# Carriage_Board_V3.net
KiCad netlist of a schematic drawn in EAGLE
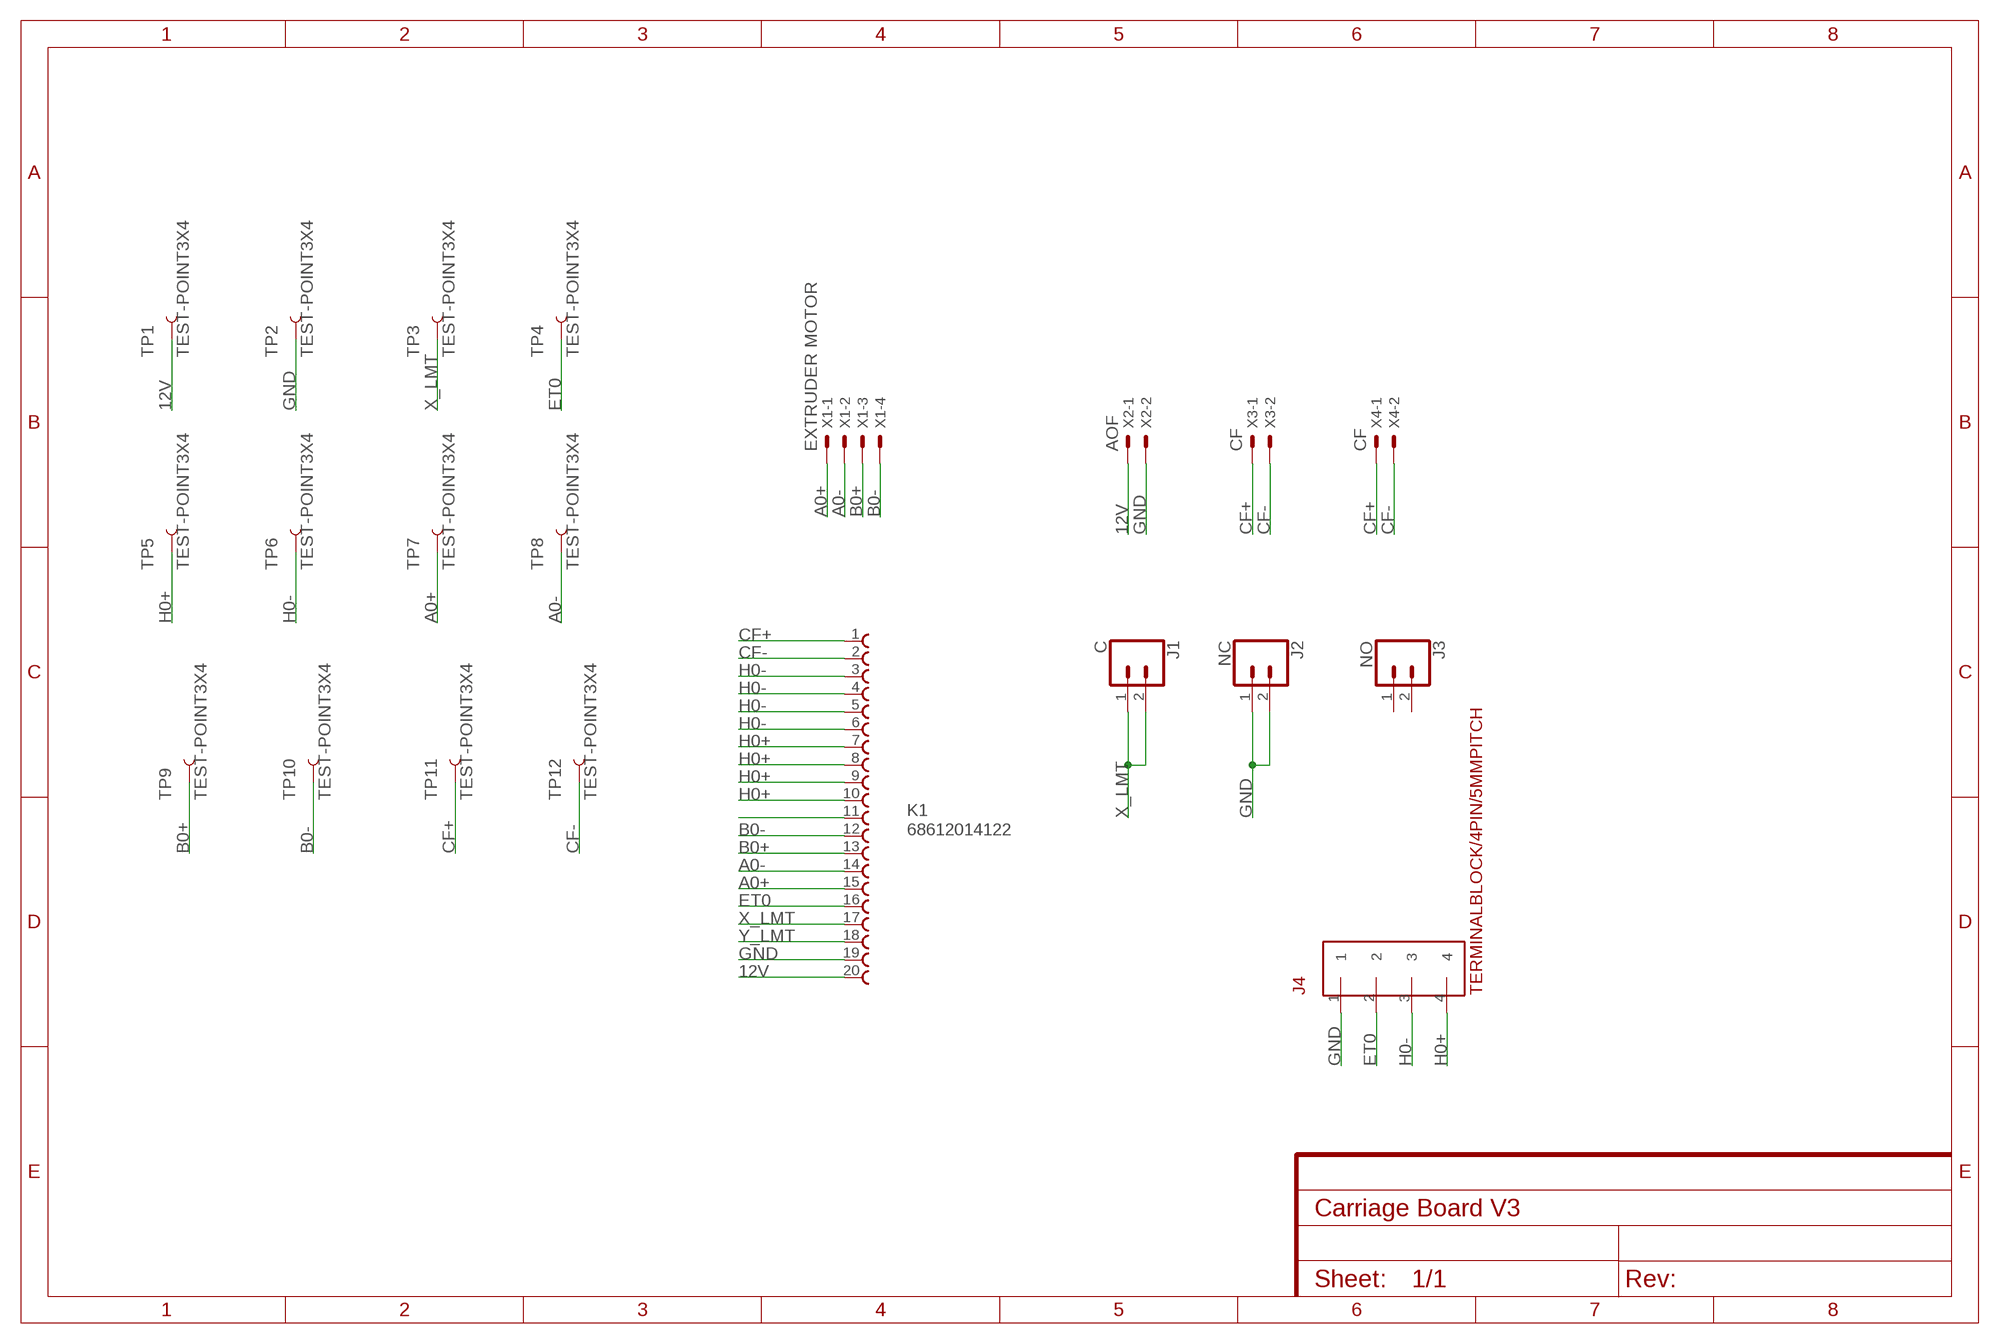
[diagram p0: schematic, sheet 1]

(export (version "E")
  (design (tool "Eeschema 10.0.6"))
  (components
    (comp (ref "J1")
      (value "C")
      (footprint "eagle-import:1X02")
      (libsource (lib "eagle-import") (part "CONN_02"))
    )
    (comp (ref "J2")
      (value "NC")
      (footprint "eagle-import:1X02")
      (libsource (lib "eagle-import") (part "CONN_02"))
    )
    (comp (ref "J3")
      (value "NO")
      (footprint "eagle-import:1X02")
      (libsource (lib "eagle-import") (part "CONN_02"))
    )
    (comp (ref "J4")
      (value "TERMINALBLOCK/4PIN/5MMPITCH")
      (footprint "eagle-import:TERMINALBLOCK_TOYO_4PIN_5MMPITCH")
      (libsource (lib "eagle-import") (part "TERMINALBLOCK/4PIN/5MMPITCH"))
    )
    (comp (ref "K1")
      (value "68612014122")
      (footprint "eagle-import:68612014122")
      (libsource (lib "eagle-import") (part "68612014122"))
    )
    (comp (ref "TP1")
      (value "TEST-POINT3X4")
      (footprint "eagle-import:PAD.03X.04")
      (libsource (lib "eagle-import") (part "TEST-POINT3X4"))
    )
    (comp (ref "TP2")
      (value "TEST-POINT3X4")
      (footprint "eagle-import:PAD.03X.04")
      (libsource (lib "eagle-import") (part "TEST-POINT3X4"))
    )
    (comp (ref "TP3")
      (value "TEST-POINT3X4")
      (footprint "eagle-import:PAD.03X.04")
      (libsource (lib "eagle-import") (part "TEST-POINT3X4"))
    )
    (comp (ref "TP4")
      (value "TEST-POINT3X4")
      (footprint "eagle-import:PAD.03X.04")
      (libsource (lib "eagle-import") (part "TEST-POINT3X4"))
    )
    (comp (ref "TP5")
      (value "TEST-POINT3X4")
      (footprint "eagle-import:PAD.03X.04")
      (libsource (lib "eagle-import") (part "TEST-POINT3X4"))
    )
    (comp (ref "TP6")
      (value "TEST-POINT3X4")
      (footprint "eagle-import:PAD.03X.04")
      (libsource (lib "eagle-import") (part "TEST-POINT3X4"))
    )
    (comp (ref "TP7")
      (value "TEST-POINT3X4")
      (footprint "eagle-import:PAD.03X.04")
      (libsource (lib "eagle-import") (part "TEST-POINT3X4"))
    )
    (comp (ref "TP8")
      (value "TEST-POINT3X4")
      (footprint "eagle-import:PAD.03X.04")
      (libsource (lib "eagle-import") (part "TEST-POINT3X4"))
    )
    (comp (ref "TP9")
      (value "TEST-POINT3X4")
      (footprint "eagle-import:PAD.03X.04")
      (libsource (lib "eagle-import") (part "TEST-POINT3X4"))
    )
    (comp (ref "TP10")
      (value "TEST-POINT3X4")
      (footprint "eagle-import:PAD.03X.04")
      (libsource (lib "eagle-import") (part "TEST-POINT3X4"))
    )
    (comp (ref "TP11")
      (value "TEST-POINT3X4")
      (footprint "eagle-import:PAD.03X.04")
      (libsource (lib "eagle-import") (part "TEST-POINT3X4"))
    )
    (comp (ref "TP12")
      (value "TEST-POINT3X4")
      (footprint "eagle-import:PAD.03X.04")
      (libsource (lib "eagle-import") (part "TEST-POINT3X4"))
    )
    (comp (ref "X1")
      (value "EXTRUDER MOTOR")
      (footprint "eagle-import:JST-XH-04-PACKAGE-LONG-PAD")
      (libsource (lib "eagle-import") (part "JST-XH-04-PIN-LONG-PAD"))
    )
    (comp (ref "X2")
      (value "AOF")
      (footprint "eagle-import:JST-XH-02-PACKAGE-LONG-PAD")
      (libsource (lib "eagle-import") (part "JST-XH-02-PIN-LONG-PAD"))
    )
    (comp (ref "X3")
      (value "CF")
      (footprint "eagle-import:JST-XH-02-PACKAGE-LONG-PAD")
      (libsource (lib "eagle-import") (part "JST-XH-02-PIN-LONG-PAD"))
    )
    (comp (ref "X4")
      (value "CF")
      (footprint "eagle-import:JST-XH-02-PACKAGE-LONG-PAD")
      (libsource (lib "eagle-import") (part "JST-XH-02-PIN-LONG-PAD"))
    )
  )
  (nets
    (net (code "1") (name "/12V") (class "Default")
      (node (ref "K1") (pin "20") (pinfunction "20_20") (pintype "passive"))
      (node (ref "TP1") (pin "P$1") (pinfunction "1_P$1") (pintype "bidirectional"))
      (node (ref "X2") (pin "1") (pinfunction "S_1") (pintype "passive"))
    )
    (net (code "2") (name "/A0+") (class "Default")
      (node (ref "K1") (pin "15") (pinfunction "15_15") (pintype "passive"))
      (node (ref "TP7") (pin "P$1") (pinfunction "1_P$1") (pintype "bidirectional"))
      (node (ref "X1") (pin "1") (pinfunction "S_1") (pintype "passive"))
    )
    (net (code "3") (name "/A0-") (class "Default")
      (node (ref "K1") (pin "14") (pinfunction "14_14") (pintype "passive"))
      (node (ref "TP8") (pin "P$1") (pinfunction "1_P$1") (pintype "bidirectional"))
      (node (ref "X1") (pin "2") (pinfunction "S_2") (pintype "passive"))
    )
    (net (code "4") (name "/B0+") (class "Default")
      (node (ref "K1") (pin "13") (pinfunction "13_13") (pintype "passive"))
      (node (ref "TP9") (pin "P$1") (pinfunction "1_P$1") (pintype "bidirectional"))
      (node (ref "X1") (pin "3") (pinfunction "S_3") (pintype "passive"))
    )
    (net (code "5") (name "/B0-") (class "Default")
      (node (ref "K1") (pin "12") (pinfunction "12_12") (pintype "passive"))
      (node (ref "TP10") (pin "P$1") (pinfunction "1_P$1") (pintype "bidirectional"))
      (node (ref "X1") (pin "4") (pinfunction "S_4") (pintype "passive"))
    )
    (net (code "6") (name "/CF+") (class "Default")
      (node (ref "K1") (pin "1") (pinfunction "1_1") (pintype "passive"))
      (node (ref "TP11") (pin "P$1") (pinfunction "1_P$1") (pintype "bidirectional"))
      (node (ref "X3") (pin "1") (pinfunction "S_1") (pintype "passive"))
      (node (ref "X4") (pin "1") (pinfunction "S_1") (pintype "passive"))
    )
    (net (code "7") (name "/CF-") (class "Default")
      (node (ref "K1") (pin "2") (pinfunction "2_2") (pintype "passive"))
      (node (ref "TP12") (pin "P$1") (pinfunction "1_P$1") (pintype "bidirectional"))
      (node (ref "X3") (pin "2") (pinfunction "S_2") (pintype "passive"))
      (node (ref "X4") (pin "2") (pinfunction "S_2") (pintype "passive"))
    )
    (net (code "8") (name "/ET0") (class "Default")
      (node (ref "J4") (pin "2") (pinfunction "2_2") (pintype "bidirectional"))
      (node (ref "K1") (pin "16") (pinfunction "16_16") (pintype "passive"))
      (node (ref "TP4") (pin "P$1") (pinfunction "1_P$1") (pintype "bidirectional"))
    )
    (net (code "9") (name "/GND") (class "Default")
      (node (ref "J2") (pin "1") (pinfunction "1_1") (pintype "passive"))
      (node (ref "J2") (pin "2") (pinfunction "2_2") (pintype "passive"))
      (node (ref "J4") (pin "1") (pinfunction "1_1") (pintype "bidirectional"))
      (node (ref "K1") (pin "19") (pinfunction "19_19") (pintype "passive"))
      (node (ref "TP2") (pin "P$1") (pinfunction "1_P$1") (pintype "bidirectional"))
      (node (ref "X2") (pin "2") (pinfunction "S_2") (pintype "passive"))
    )
    (net (code "10") (name "/H0+") (class "Default")
      (node (ref "J4") (pin "4") (pinfunction "4_4") (pintype "bidirectional"))
      (node (ref "K1") (pin "10") (pinfunction "10_10") (pintype "passive"))
      (node (ref "K1") (pin "7") (pinfunction "7_7") (pintype "passive"))
      (node (ref "K1") (pin "8") (pinfunction "8_8") (pintype "passive"))
      (node (ref "K1") (pin "9") (pinfunction "9_9") (pintype "passive"))
      (node (ref "TP5") (pin "P$1") (pinfunction "1_P$1") (pintype "bidirectional"))
    )
    (net (code "11") (name "/H0-") (class "Default")
      (node (ref "J4") (pin "3") (pinfunction "3_3") (pintype "bidirectional"))
      (node (ref "K1") (pin "3") (pinfunction "3_3") (pintype "passive"))
      (node (ref "K1") (pin "4") (pinfunction "4_4") (pintype "passive"))
      (node (ref "K1") (pin "5") (pinfunction "5_5") (pintype "passive"))
      (node (ref "K1") (pin "6") (pinfunction "6_6") (pintype "passive"))
      (node (ref "TP6") (pin "P$1") (pinfunction "1_P$1") (pintype "bidirectional"))
    )
    (net (code "12") (name "/X_LMT") (class "Default")
      (node (ref "J1") (pin "1") (pinfunction "1_1") (pintype "passive"))
      (node (ref "J1") (pin "2") (pinfunction "2_2") (pintype "passive"))
      (node (ref "K1") (pin "17") (pinfunction "17_17") (pintype "passive"))
      (node (ref "TP3") (pin "P$1") (pinfunction "1_P$1") (pintype "bidirectional"))
    )
    (net (code "13") (name "/Y_LMT") (class "Default")
      (node (ref "K1") (pin "18") (pinfunction "18_18") (pintype "passive"))
    )
    (net (code "14") (name "unconnected-(J3-Pad1)") (class "Default")
      (node (ref "J3") (pin "1") (pinfunction "1_1") (pintype "passive"))
    )
    (net (code "15") (name "unconnected-(J3-Pad2)") (class "Default")
      (node (ref "J3") (pin "2") (pinfunction "2_2") (pintype "passive"))
    )
    (net (code "16") (name "unconnected-(K1-Pad11)") (class "Default")
      (node (ref "K1") (pin "11") (pinfunction "11_11") (pintype "passive"))
    )
  )
)
